# Connectors.net
KiCad netlist of a schematic drawn in Altium Designer
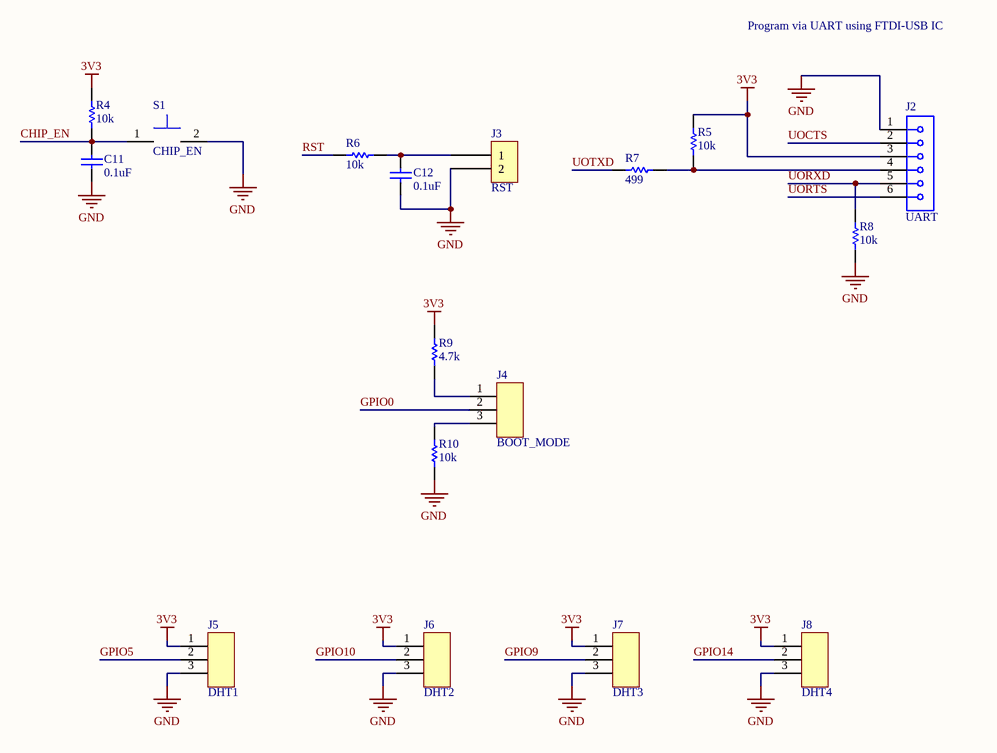
[diagram p0: Connectors.SchDoc]

(export (version "E")
  (design (tool "Eeschema 10.0.6"))
  (components
    (comp (ref "C11")
      (value "0.1uF")
      (footprint "PCB-oygqt4xf3sesynjclq4r-1")
      (description "0.1uF, ±10%, 50V, X7R, 0805, Multilayer Ceramic Capacitor")
      (fields (field (name "MANUFACTURER PART NUMBER") "CL21B104KBCNNNC"))
      (libsource (lib "CommunityVault") (part "SYM-94265da154d84be1-1"))
    )
    (comp (ref "C12")
      (value "0.1uF")
      (footprint "PCB-oygqt4xf3sesynjclq4r-1")
      (description "0.1uF, ±10%, 50V, X7R, 0805, Multilayer Ceramic Capacitor")
      (fields (field (name "MANUFACTURER PART NUMBER") "CL21B104KBCNNNC"))
      (libsource (lib "CommunityVault") (part "SYM-94265da154d84be1-1"))
    )
    (comp (ref "J2")
      (value "UART")
      (footprint "PCB-di8nzhz8ya7afv8i1myi-1")
      (description "Conn; Rect; UnshroudedHdr; 6Cnts; ThruHole; BergStik; 2.54mmPin-Spng; Vert; 1-Row")
      (libsource (lib "CommunityVault") (part "SYM-ea272149382c35e0-2"))
    )
    (comp (ref "J3")
      (value "RST")
      (footprint "Jumper")
      (description "2 pin male header straight tht")
      (libsource (lib "CommunityVault") (part "SYM-76d7babf30d4a910-1"))
    )
    (comp (ref "J4")
      (value "BOOT_MODE")
      (footprint "PCB-s0hfil65plaomi4ibvcw-1")
      (description "THT Vertical Pin Header WR-PHD, Pitch 2.54 mm, Single Row, 3 pins")
      (libsource (lib "CommunityVault") (part "SYM-8a90426ffa175557-17"))
    )
    (comp (ref "J5")
      (value "DHT1")
      (footprint "PCB-s0hfil65plaomi4ibvcw-1")
      (description "THT Vertical Pin Header WR-PHD, Pitch 2.54 mm, Single Row, 3 pins")
      (libsource (lib "CommunityVault") (part "SYM-8a90426ffa175557-17"))
    )
    (comp (ref "J6")
      (value "DHT2")
      (footprint "PCB-s0hfil65plaomi4ibvcw-1")
      (description "THT Vertical Pin Header WR-PHD, Pitch 2.54 mm, Single Row, 3 pins")
      (libsource (lib "CommunityVault") (part "SYM-8a90426ffa175557-17"))
    )
    (comp (ref "J7")
      (value "DHT3")
      (footprint "PCB-s0hfil65plaomi4ibvcw-1")
      (description "THT Vertical Pin Header WR-PHD, Pitch 2.54 mm, Single Row, 3 pins")
      (libsource (lib "CommunityVault") (part "SYM-8a90426ffa175557-17"))
    )
    (comp (ref "J8")
      (value "DHT4")
      (footprint "PCB-s0hfil65plaomi4ibvcw-1")
      (description "THT Vertical Pin Header WR-PHD, Pitch 2.54 mm, Single Row, 3 pins")
      (libsource (lib "CommunityVault") (part "SYM-8a90426ffa175557-17"))
    )
    (comp (ref "R4")
      (value "10k")
      (footprint "PCB-urbe6pl2f36u5sj9z9e0-1")
      (description "Res, AEC-Q200, Thick Film, 10K, 5%, 0603")
      (fields (field (name "MANUFACTURER PART NUMBER") "CRGCQ0603J10K"))
      (libsource (lib "CommunityVault") (part "SYM-1974d512ef63c6b3-1"))
    )
    (comp (ref "R5")
      (value "10k")
      (footprint "PCB-urbe6pl2f36u5sj9z9e0-1")
      (description "Res, AEC-Q200, Thick Film, 10K, 5%, 0603")
      (fields (field (name "MANUFACTURER PART NUMBER") "CRGCQ0603J10K"))
      (libsource (lib "CommunityVault") (part "SYM-1974d512ef63c6b3-1"))
    )
    (comp (ref "R6")
      (value "10k")
      (footprint "PCB-urbe6pl2f36u5sj9z9e0-1")
      (description "Res, AEC-Q200, Thick Film, 10K, 5%, 0603")
      (fields (field (name "MANUFACTURER PART NUMBER") "CRGCQ0603J10K"))
      (libsource (lib "CommunityVault") (part "SYM-1974d512ef63c6b3-1"))
    )
    (comp (ref "R7")
      (value "499")
      (footprint "RESC1609X50X30ML10T20")
      (description "Res Thick Film 0603 499 Ohm 1% 1/10W ±100ppm/C Molded SMD Paper T/R")
      (fields (field (name "MANUFACTURER PART NUMBER") "CRCW0603499RFKEA"))
      (libsource (lib "CommunityVault") (part "RES-2"))
    )
    (comp (ref "R8")
      (value "10k")
      (footprint "PCB-urbe6pl2f36u5sj9z9e0-1")
      (description "Res, AEC-Q200, Thick Film, 10K, 5%, 0603")
      (fields (field (name "MANUFACTURER PART NUMBER") "CRGCQ0603J10K"))
      (libsource (lib "CommunityVault") (part "SYM-1974d512ef63c6b3-1"))
    )
    (comp (ref "R9")
      (value "4.7k")
      (footprint "RESC1608X55X30ML20T10")
      (description "Res Thick Film 0603 4.7K Ohm 5% 0.1W(1/10W) ±200ppm/C Molded SMD Automotive Punched Paper T/R")
      (fields (field (name "MANUFACTURER PART NUMBER") "RK73B1JTTD472J"))
      (libsource (lib "CommunityVault") (part "RES-2"))
    )
    (comp (ref "R10")
      (value "10k")
      (footprint "PCB-urbe6pl2f36u5sj9z9e0-1")
      (description "Res, AEC-Q200, Thick Film, 10K, 5%, 0603")
      (fields (field (name "MANUFACTURER PART NUMBER") "CRGCQ0603J10K"))
      (libsource (lib "CommunityVault") (part "SYM-1974d512ef63c6b3-1"))
    )
    (comp (ref "S1")
      (value "CHIP_EN")
      (footprint "PCB-xzcf6rj7v3ysitq80b7l-1")
      (description "Switch Tactile Spst-No 0.02a 15v")
      (libsource (lib "CommunityVault") (part "SYM-32abff024869ed6c-1"))
    )
  )
  (nets
    (net (code "1") (name "/CHIP_EN") (class "Default")
      (node (ref "C11") (pin "2") (pinfunction "2_2") (pintype "passive"))
      (node (ref "R4") (pin "1") (pinfunction "1_1") (pintype "passive"))
      (node (ref "S1") (pin "1") (pinfunction "1_1") (pintype "power_in"))
    )
    (net (code "2") (name "/GPIO0") (class "Default")
      (node (ref "J4") (pin "2") (pinfunction "2_2") (pintype "passive"))
    )
    (net (code "3") (name "/GPIO5") (class "Default")
      (node (ref "J5") (pin "2") (pinfunction "2_2") (pintype "passive"))
    )
    (net (code "4") (name "/GPIO9") (class "Default")
      (node (ref "J7") (pin "2") (pinfunction "2_2") (pintype "passive"))
    )
    (net (code "5") (name "/GPIO10") (class "Default")
      (node (ref "J6") (pin "2") (pinfunction "2_2") (pintype "passive"))
    )
    (net (code "6") (name "/GPIO14") (class "Default")
      (node (ref "J8") (pin "2") (pinfunction "2_2") (pintype "passive"))
    )
    (net (code "7") (name "/RST") (class "Default")
      (node (ref "R6") (pin "2") (pinfunction "2_2") (pintype "passive"))
    )
    (net (code "8") (name "/UOCTS") (class "Default")
      (node (ref "J2") (pin "2") (pinfunction "2_2") (pintype "passive"))
    )
    (net (code "9") (name "/UORTS") (class "Default")
      (node (ref "J2") (pin "6") (pinfunction "6_6") (pintype "passive"))
    )
    (net (code "10") (name "/UORXD") (class "Default")
      (node (ref "J2") (pin "5") (pinfunction "5_5") (pintype "passive"))
      (node (ref "R8") (pin "1") (pinfunction "1_1") (pintype "passive"))
    )
    (net (code "11") (name "/UOTXD") (class "Default")
      (node (ref "R7") (pin "1") (pinfunction "1_1") (pintype "passive"))
    )
    (net (code "12") (name "3V3") (class "Default")
      (node (ref "J2") (pin "3") (pinfunction "3_3") (pintype "passive"))
      (node (ref "J5") (pin "1") (pinfunction "1_1") (pintype "passive"))
      (node (ref "J6") (pin "1") (pinfunction "1_1") (pintype "passive"))
      (node (ref "J7") (pin "1") (pinfunction "1_1") (pintype "passive"))
      (node (ref "J8") (pin "1") (pinfunction "1_1") (pintype "passive"))
      (node (ref "R4") (pin "2") (pinfunction "2_2") (pintype "passive"))
      (node (ref "R5") (pin "1") (pinfunction "1_1") (pintype "passive"))
      (node (ref "R9") (pin "2") (pinfunction "2_2") (pintype "passive"))
    )
    (net (code "13") (name "GND") (class "Default")
      (node (ref "C11") (pin "1") (pinfunction "1_1") (pintype "passive"))
      (node (ref "C12") (pin "1") (pinfunction "1_1") (pintype "passive"))
      (node (ref "J2") (pin "1") (pinfunction "1_1") (pintype "passive"))
      (node (ref "J3") (pin "2") (pinfunction "2_2") (pintype "power_in"))
      (node (ref "J5") (pin "3") (pinfunction "3_3") (pintype "passive"))
      (node (ref "J6") (pin "3") (pinfunction "3_3") (pintype "passive"))
      (node (ref "J7") (pin "3") (pinfunction "3_3") (pintype "passive"))
      (node (ref "J8") (pin "3") (pinfunction "3_3") (pintype "passive"))
      (node (ref "R10") (pin "2") (pinfunction "2_2") (pintype "passive"))
      (node (ref "R8") (pin "2") (pinfunction "2_2") (pintype "passive"))
      (node (ref "S1") (pin "2") (pinfunction "2_2") (pintype "power_in"))
    )
    (net (code "14") (name "Net-(C12-Pad2)") (class "Default")
      (node (ref "C12") (pin "2") (pinfunction "2_2") (pintype "passive"))
      (node (ref "J3") (pin "1") (pinfunction "1_1") (pintype "power_in"))
      (node (ref "R6") (pin "1") (pinfunction "1_1") (pintype "passive"))
    )
    (net (code "15") (name "Net-(J2-Pad4)") (class "Default")
      (node (ref "J2") (pin "4") (pinfunction "4_4") (pintype "passive"))
      (node (ref "R5") (pin "2") (pinfunction "2_2") (pintype "passive"))
      (node (ref "R7") (pin "2") (pinfunction "2_2") (pintype "passive"))
    )
    (net (code "16") (name "Net-(J4-Pad1)") (class "Default")
      (node (ref "J4") (pin "1") (pinfunction "1_1") (pintype "passive"))
      (node (ref "R9") (pin "1") (pinfunction "1_1") (pintype "passive"))
    )
    (net (code "17") (name "Net-(J4-Pad3)") (class "Default")
      (node (ref "J4") (pin "3") (pinfunction "3_3") (pintype "passive"))
      (node (ref "R10") (pin "1") (pinfunction "1_1") (pintype "passive"))
    )
  )
)
